# Example.net
KiCad netlist of a schematic drawn in Altium Designer
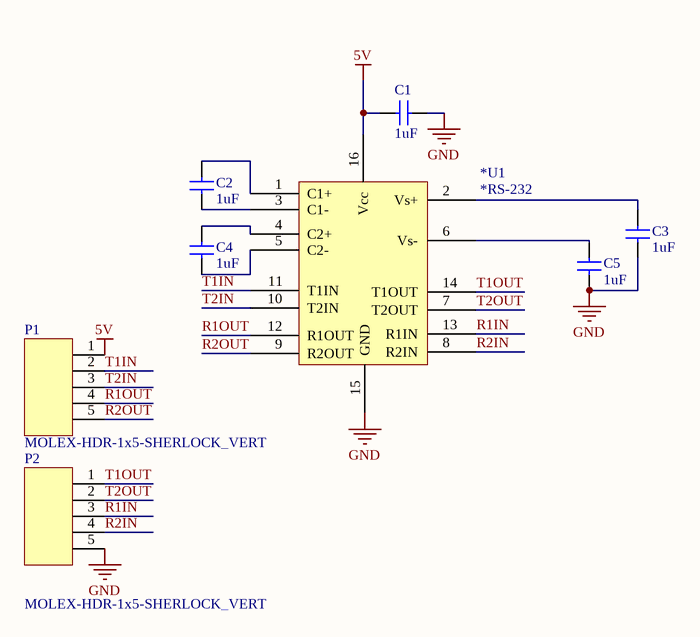
[diagram p0: Example.SchDoc]

(export (version "E")
  (design (tool "Eeschema 10.0.6"))
  (components
    (comp (ref "*U1")
      (value "*RS-232")
      (footprint "RS-232")
      (description "IC DVR/RCVR RS232 DUAL 16SOIC")
      (libsource (lib "ICs") (part "RS-232"))
    )
    (comp (ref "C1")
      (value "1uF")
      (footprint "CAPC0603")
      (fields (field (name "Comment") "Cap"))
      (libsource (lib "Passives") (part "Cap"))
    )
    (comp (ref "C2")
      (value "1uF")
      (footprint "CAPC0603")
      (fields (field (name "Comment") "Cap"))
      (libsource (lib "Passives") (part "Cap"))
    )
    (comp (ref "C3")
      (value "1uF")
      (footprint "CAPC0603")
      (fields (field (name "Comment") "Cap"))
      (libsource (lib "Passives") (part "Cap"))
    )
    (comp (ref "C4")
      (value "1uF")
      (footprint "CAPC0603")
      (fields (field (name "Comment") "Cap"))
      (libsource (lib "Passives") (part "Cap"))
    )
    (comp (ref "C5")
      (value "1uF")
      (footprint "CAPC0603")
      (fields (field (name "Comment") "Cap"))
      (libsource (lib "Passives") (part "Cap"))
    )
    (comp (ref "P1")
      (value "MOLEX-HDR-1x5-SHERLOCK_VERT")
      (footprint "MOLEX-HDR-1X5-SHERLOCK-VERT")
      (libsource (lib "Connectors") (part "MOLEX-HDR-1x5-SHERLOCK_VERT"))
    )
    (comp (ref "P2")
      (value "MOLEX-HDR-1x5-SHERLOCK_VERT")
      (footprint "MOLEX-HDR-1X5-SHERLOCK-VERT")
      (libsource (lib "Connectors") (part "MOLEX-HDR-1x5-SHERLOCK_VERT"))
    )
  )
  (nets
    (net (code "1") (name "/R1IN") (class "Default")
      (node (ref "*U1") (pin "13") (pinfunction "R1IN_13") (pintype "passive"))
      (node (ref "P2") (pin "3") (pinfunction "3_3") (pintype "passive"))
    )
    (net (code "2") (name "/R1OUT") (class "Default")
      (node (ref "*U1") (pin "12") (pinfunction "R1OUT_12") (pintype "passive"))
      (node (ref "P1") (pin "4") (pinfunction "4_4") (pintype "passive"))
    )
    (net (code "3") (name "/R2IN") (class "Default")
      (node (ref "*U1") (pin "8") (pinfunction "R2IN_8") (pintype "passive"))
      (node (ref "P2") (pin "4") (pinfunction "4_4") (pintype "passive"))
    )
    (net (code "4") (name "/R2OUT") (class "Default")
      (node (ref "*U1") (pin "9") (pinfunction "R2OUT_9") (pintype "passive"))
      (node (ref "P1") (pin "5") (pinfunction "5_5") (pintype "passive"))
    )
    (net (code "5") (name "/T1IN") (class "Default")
      (node (ref "*U1") (pin "11") (pinfunction "T1IN_11") (pintype "passive"))
      (node (ref "P1") (pin "2") (pinfunction "2_2") (pintype "passive"))
    )
    (net (code "6") (name "/T1OUT") (class "Default")
      (node (ref "*U1") (pin "14") (pinfunction "T1OUT_14") (pintype "passive"))
      (node (ref "P2") (pin "1") (pinfunction "1_1") (pintype "passive"))
    )
    (net (code "7") (name "/T2IN") (class "Default")
      (node (ref "*U1") (pin "10") (pinfunction "T2IN_10") (pintype "passive"))
      (node (ref "P1") (pin "3") (pinfunction "3_3") (pintype "passive"))
    )
    (net (code "8") (name "/T2OUT") (class "Default")
      (node (ref "*U1") (pin "7") (pinfunction "T2OUT_7") (pintype "passive"))
      (node (ref "P2") (pin "2") (pinfunction "2_2") (pintype "passive"))
    )
    (net (code "9") (name "5V") (class "Default")
      (node (ref "*U1") (pin "16") (pinfunction "Vcc_16") (pintype "passive"))
      (node (ref "C1") (pin "1") (pinfunction "A_1") (pintype "passive"))
      (node (ref "P1") (pin "1") (pinfunction "1_1") (pintype "passive"))
    )
    (net (code "10") (name "GND") (class "Default")
      (node (ref "*U1") (pin "15") (pinfunction "GND_15") (pintype "passive"))
      (node (ref "C1") (pin "2") (pinfunction "B_2") (pintype "passive"))
      (node (ref "C3") (pin "2") (pinfunction "B_2") (pintype "passive"))
      (node (ref "C5") (pin "2") (pinfunction "B_2") (pintype "passive"))
      (node (ref "P2") (pin "5") (pinfunction "5_5") (pintype "passive"))
    )
    (net (code "11") (name "Net-(*U1-C1+)") (class "Default")
      (node (ref "*U1") (pin "1") (pinfunction "C1+_1") (pintype "passive"))
      (node (ref "C2") (pin "1") (pinfunction "A_1") (pintype "passive"))
    )
    (net (code "12") (name "Net-(*U1-C1-)") (class "Default")
      (node (ref "*U1") (pin "3") (pinfunction "C1-_3") (pintype "passive"))
      (node (ref "C2") (pin "2") (pinfunction "B_2") (pintype "passive"))
    )
    (net (code "13") (name "Net-(*U1-C2+)") (class "Default")
      (node (ref "*U1") (pin "4") (pinfunction "C2+_4") (pintype "passive"))
      (node (ref "C4") (pin "1") (pinfunction "A_1") (pintype "passive"))
    )
    (net (code "14") (name "Net-(*U1-C2-)") (class "Default")
      (node (ref "*U1") (pin "5") (pinfunction "C2-_5") (pintype "passive"))
      (node (ref "C4") (pin "2") (pinfunction "B_2") (pintype "passive"))
    )
    (net (code "15") (name "Net-(*U1-Vs+)") (class "Default")
      (node (ref "*U1") (pin "2") (pinfunction "Vs+_2") (pintype "passive"))
      (node (ref "C3") (pin "1") (pinfunction "A_1") (pintype "passive"))
    )
    (net (code "16") (name "Net-(*U1-Vs-)") (class "Default")
      (node (ref "*U1") (pin "6") (pinfunction "Vs-_6") (pintype "passive"))
      (node (ref "C5") (pin "1") (pinfunction "A_1") (pintype "passive"))
    )
  )
)
